# PERIPHERAL_PORT_IO.net
KiCad netlist of a schematic drawn in Altium Designer
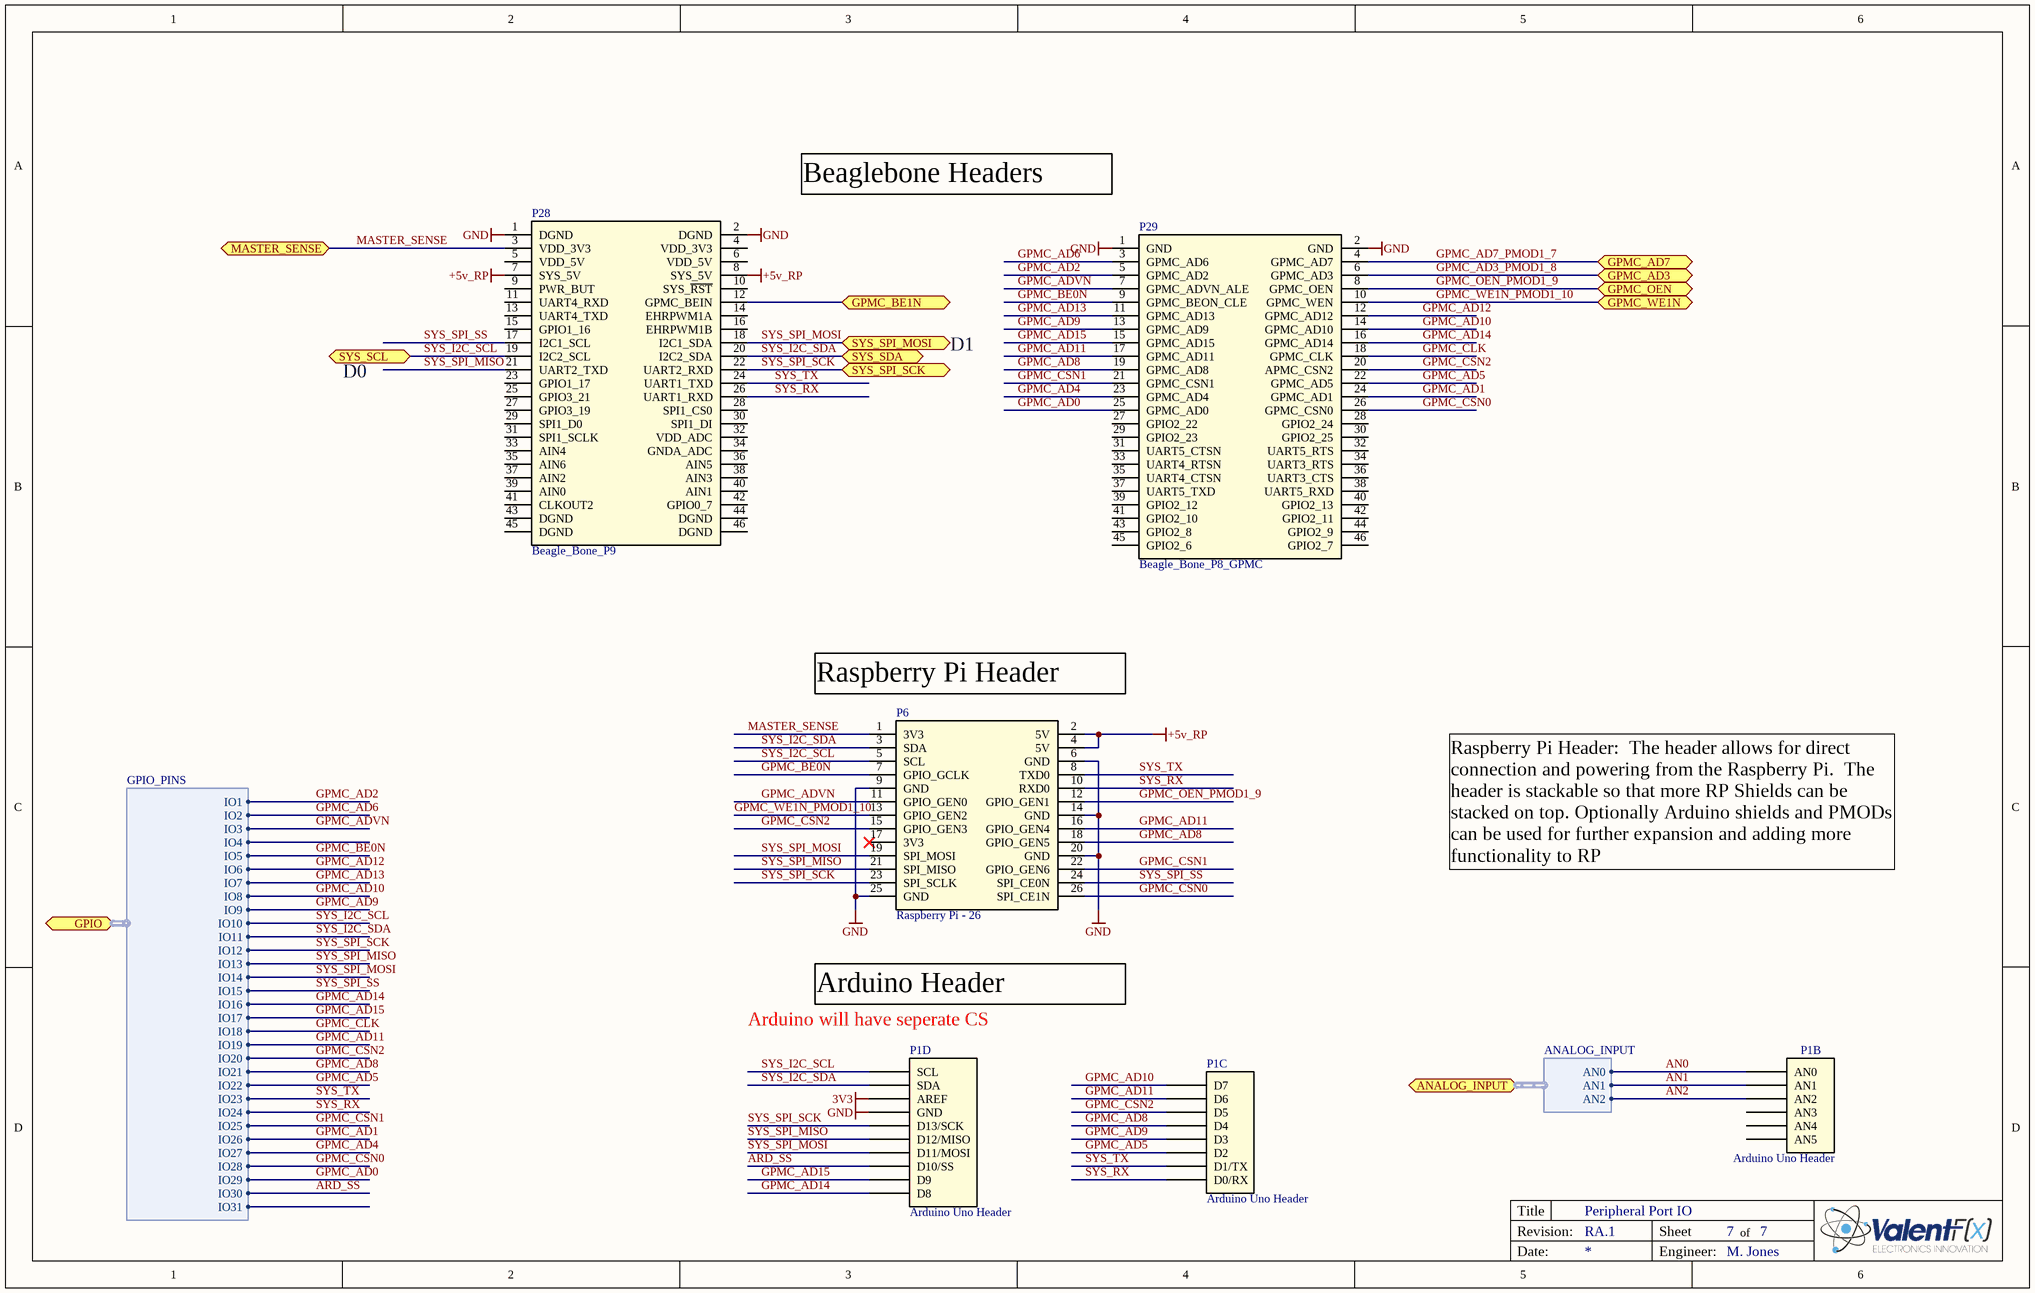
[diagram p0: PERIPHERAL_PORT_IO.SchDoc]

(export (version "E")
  (design (tool "Eeschema 10.0.6"))
  (components
    (comp (ref "P1")
      (value "Arduino Uno Header")
      (footprint "Arduino Shield - smaller Thru")
      (description "Arduino Duem Header")
      (libsource (lib "eConnector") (part "Arduino Shield"))
    )
    (comp (ref "P6")
      (value "Raspberry Pi - 26")
      (footprint "Raspberr Pi - 26")
      (libsource (lib "mConnector") (part "Raspberry Pi - 26"))
    )
    (comp (ref "P28")
      (value "Beagle_Bone_P9")
      (footprint "TSM-116-01-F-DV_TH - SHRUNK")
      (libsource (lib "mConnector") (part "Beagle_Bone_P9"))
    )
    (comp (ref "P29")
      (value "Beagle_Bone_P8_GPMC")
      (footprint "TSM-113-01-F-DV_TH - SHRUNK")
      (libsource (lib "mConnector") (part "Beagle_Bone_P8_GPMC"))
    )
  )
  (nets
    (net (code "3") (name "+5v_RP") (class "Default")
      (node (ref "P28") (pin "7") (pinfunction "SYS_5V_7") (pintype "passive"))
      (node (ref "P28") (pin "8") (pinfunction "SYS_5V_8") (pintype "passive"))
      (node (ref "P6") (pin "2") (pinfunction "5V_2") (pintype "passive"))
      (node (ref "P6") (pin "4") (pinfunction "5V_4") (pintype "passive"))
    )
    (net (code "4") (name "/AN0") (class "Default")
      (node (ref "P1") (pin "B1") (pinfunction "AN0_B1") (pintype "passive"))
    )
    (net (code "5") (name "/AN1") (class "Default")
      (node (ref "P1") (pin "B2") (pinfunction "AN1_B2") (pintype "passive"))
    )
    (net (code "6") (name "/AN2") (class "Default")
      (node (ref "P1") (pin "B3") (pinfunction "AN2_B3") (pintype "passive"))
    )
    (net (code "7") (name "/ARD_SS") (class "Default")
      (node (ref "P1") (pin "D3") (pinfunction "D10/SS_D3") (pintype "passive"))
    )
    (net (code "8") (name "/GPMC_AD0") (class "Default")
      (node (ref "P29") (pin "25") (pinfunction "GPMC_AD0_25") (pintype "passive"))
    )
    (net (code "9") (name "/GPMC_AD1") (class "Default")
      (node (ref "P29") (pin "24") (pinfunction "GPMC_AD1_24") (pintype "passive"))
    )
    (net (code "10") (name "/GPMC_AD2") (class "Default")
      (node (ref "P29") (pin "5") (pinfunction "GPMC_AD2_5") (pintype "passive"))
    )
    (net (code "11") (name "/GPMC_AD3_PMOD1_8") (class "Default")
      (node (ref "P29") (pin "6") (pinfunction "GPMC_AD3_6") (pintype "passive"))
    )
    (net (code "12") (name "/GPMC_AD4") (class "Default")
      (node (ref "P29") (pin "23") (pinfunction "GPMC_AD4_23") (pintype "passive"))
    )
    (net (code "13") (name "/GPMC_AD5") (class "Default")
      (node (ref "P1") (pin "C3") (pinfunction "D2_C3") (pintype "passive"))
      (node (ref "P29") (pin "22") (pinfunction "GPMC_AD5_22") (pintype "passive"))
    )
    (net (code "14") (name "/GPMC_AD6") (class "Default")
      (node (ref "P29") (pin "3") (pinfunction "GPMC_AD6_3") (pintype "passive"))
    )
    (net (code "15") (name "/GPMC_AD7_PMOD1_7") (class "Default")
      (node (ref "P29") (pin "4") (pinfunction "GPMC_AD7_4") (pintype "passive"))
    )
    (net (code "16") (name "/GPMC_AD8") (class "Default")
      (node (ref "P1") (pin "C5") (pinfunction "D4_C5") (pintype "passive"))
      (node (ref "P29") (pin "19") (pinfunction "GPMC_AD8_19") (pintype "passive"))
      (node (ref "P6") (pin "18") (pinfunction "GPIO_GEN5_18") (pintype "passive"))
    )
    (net (code "17") (name "/GPMC_AD9") (class "Default")
      (node (ref "P1") (pin "C4") (pinfunction "D3_C4") (pintype "passive"))
      (node (ref "P29") (pin "13") (pinfunction "GPMC_AD9_13") (pintype "passive"))
    )
    (net (code "18") (name "/GPMC_AD10") (class "Default")
      (node (ref "P1") (pin "C8") (pinfunction "D7_C8") (pintype "passive"))
      (node (ref "P29") (pin "14") (pinfunction "GPMC_AD10_14") (pintype "passive"))
    )
    (net (code "19") (name "/GPMC_AD11") (class "Default")
      (node (ref "P1") (pin "C7") (pinfunction "D6_C7") (pintype "passive"))
      (node (ref "P29") (pin "17") (pinfunction "GPMC_AD11_17") (pintype "passive"))
      (node (ref "P6") (pin "16") (pinfunction "GPIO_GEN4_16") (pintype "passive"))
    )
    (net (code "20") (name "/GPMC_AD12") (class "Default")
      (node (ref "P29") (pin "12") (pinfunction "GPMC_AD12_12") (pintype "passive"))
    )
    (net (code "21") (name "/GPMC_AD13") (class "Default")
      (node (ref "P29") (pin "11") (pinfunction "GPMC_AD13_11") (pintype "passive"))
    )
    (net (code "22") (name "/GPMC_AD14") (class "Default")
      (node (ref "P1") (pin "D1") (pinfunction "D8_D1") (pintype "passive"))
      (node (ref "P29") (pin "16") (pinfunction "GPMC_AD14_16") (pintype "passive"))
    )
    (net (code "23") (name "/GPMC_AD15") (class "Default")
      (node (ref "P1") (pin "D2") (pinfunction "D9_D2") (pintype "passive"))
      (node (ref "P29") (pin "15") (pinfunction "GPMC_AD15_15") (pintype "passive"))
    )
    (net (code "24") (name "/GPMC_ADVN") (class "Default")
      (node (ref "P29") (pin "7") (pinfunction "GPMC_ADVN_ALE_7") (pintype "passive"))
      (node (ref "P6") (pin "11") (pinfunction "GPIO_GEN0_11") (pintype "passive"))
    )
    (net (code "25") (name "/GPMC_BE0N") (class "Default")
      (node (ref "P29") (pin "9") (pinfunction "GPMC_BEON_CLE_9") (pintype "passive"))
      (node (ref "P6") (pin "7") (pinfunction "GPIO_GCLK_7") (pintype "passive"))
    )
    (net (code "26") (name "/GPMC_BE1N") (class "Default")
      (node (ref "P28") (pin "12") (pinfunction "GPMC_BEIN_12") (pintype "passive"))
    )
    (net (code "27") (name "/GPMC_CLK") (class "Default")
      (node (ref "P29") (pin "18") (pinfunction "GPMC_CLK_18") (pintype "passive"))
    )
    (net (code "28") (name "/GPMC_CSN0") (class "Default")
      (node (ref "P29") (pin "26") (pinfunction "GPMC_CSN0_26") (pintype "passive"))
      (node (ref "P6") (pin "26") (pinfunction "SPI_CE1N_26") (pintype "passive"))
    )
    (net (code "29") (name "/GPMC_CSN1") (class "Default")
      (node (ref "P29") (pin "21") (pinfunction "GPMC_CSN1_21") (pintype "passive"))
      (node (ref "P6") (pin "22") (pinfunction "GPIO_GEN6_22") (pintype "passive"))
    )
    (net (code "30") (name "/GPMC_CSN2") (class "Default")
      (node (ref "P1") (pin "C6") (pinfunction "D5_C6") (pintype "passive"))
      (node (ref "P29") (pin "20") (pinfunction "APMC_CSN2_20") (pintype "passive"))
      (node (ref "P6") (pin "15") (pinfunction "GPIO_GEN3_15") (pintype "passive"))
    )
    (net (code "31") (name "/GPMC_OEN_PMOD1_9") (class "Default")
      (node (ref "P29") (pin "8") (pinfunction "GPMC_OEN_8") (pintype "passive"))
      (node (ref "P6") (pin "12") (pinfunction "GPIO_GEN1_12") (pintype "passive"))
    )
    (net (code "32") (name "/GPMC_WE1N_PMOD1_10") (class "Default")
      (node (ref "P29") (pin "10") (pinfunction "GPMC_WEN_10") (pintype "passive"))
      (node (ref "P6") (pin "13") (pinfunction "GPIO_GEN2_13") (pintype "passive"))
    )
    (net (code "33") (name "/MASTER_SENSE") (class "Default")
      (node (ref "P28") (pin "3") (pinfunction "VDD_3V3_3") (pintype "passive"))
      (node (ref "P6") (pin "1") (pinfunction "3V3_1") (pintype "passive"))
    )
    (net (code "34") (name "/SYS_I2C_SCL") (class "Default")
      (node (ref "P1") (pin "D10") (pinfunction "SCL_D10") (pintype "passive"))
      (node (ref "P28") (pin "19") (pinfunction "I2C2_SCL_19") (pintype "passive"))
      (node (ref "P6") (pin "5") (pinfunction "SCL_5") (pintype "passive"))
    )
    (net (code "35") (name "/SYS_I2C_SDA") (class "Default")
      (node (ref "P1") (pin "D9") (pinfunction "SDA_D9") (pintype "passive"))
      (node (ref "P28") (pin "20") (pinfunction "I2C2_SDA_20") (pintype "passive"))
      (node (ref "P6") (pin "3") (pinfunction "SDA_3") (pintype "passive"))
    )
    (net (code "36") (name "/SYS_RX") (class "Default")
      (node (ref "P1") (pin "C1") (pinfunction "D0/RX_C1") (pintype "passive"))
      (node (ref "P28") (pin "26") (pinfunction "UART1_RXD_26") (pintype "passive"))
      (node (ref "P6") (pin "10") (pinfunction "RXD0_10") (pintype "passive"))
    )
    (net (code "37") (name "/SYS_SPI_MISO") (class "Default")
      (node (ref "P1") (pin "D5") (pinfunction "D12/MISO_D5") (pintype "passive"))
      (node (ref "P28") (pin "21") (pinfunction "UART2_TXD_21") (pintype "passive"))
      (node (ref "P6") (pin "21") (pinfunction "SPI_MISO_21") (pintype "passive"))
    )
    (net (code "38") (name "/SYS_SPI_MOSI") (class "Default")
      (node (ref "P1") (pin "D4") (pinfunction "D11/MOSI_D4") (pintype "passive"))
      (node (ref "P28") (pin "18") (pinfunction "I2C1_SDA_18") (pintype "passive"))
      (node (ref "P6") (pin "19") (pinfunction "SPI_MOSI_19") (pintype "passive"))
    )
    (net (code "39") (name "/SYS_SPI_SCK") (class "Default")
      (node (ref "P1") (pin "D6") (pinfunction "D13/SCK_D6") (pintype "passive"))
      (node (ref "P28") (pin "22") (pinfunction "UART2_RXD_22") (pintype "passive"))
      (node (ref "P6") (pin "23") (pinfunction "SPI_SCLK_23") (pintype "passive"))
    )
    (net (code "40") (name "/SYS_SPI_SS") (class "Default")
      (node (ref "P28") (pin "17") (pinfunction "I2C1_SCL_17") (pintype "passive"))
      (node (ref "P6") (pin "24") (pinfunction "SPI_CE0N_24") (pintype "passive"))
    )
    (net (code "41") (name "/SYS_TX") (class "Default")
      (node (ref "P1") (pin "C2") (pinfunction "D1/TX_C2") (pintype "passive"))
      (node (ref "P28") (pin "24") (pinfunction "UART1_TXD_24") (pintype "passive"))
      (node (ref "P6") (pin "8") (pinfunction "TXD0_8") (pintype "passive"))
    )
    (net (code "44") (name "3V3") (class "Default")
      (node (ref "P1") (pin "D8") (pinfunction "AREF_D8") (pintype "passive"))
    )
    (net (code "45") (name "GND") (class "Default")
      (node (ref "P1") (pin "D7") (pinfunction "GND_D7") (pintype "passive"))
      (node (ref "P28") (pin "1") (pinfunction "DGND_1") (pintype "passive"))
      (node (ref "P28") (pin "2") (pinfunction "DGND_2") (pintype "passive"))
      (node (ref "P29") (pin "1") (pinfunction "GND_1") (pintype "passive"))
      (node (ref "P29") (pin "2") (pinfunction "GND_2") (pintype "passive"))
      (node (ref "P6") (pin "14") (pinfunction "GND_14") (pintype "passive"))
      (node (ref "P6") (pin "20") (pinfunction "GND_20") (pintype "passive"))
      (node (ref "P6") (pin "25") (pinfunction "GND_25") (pintype "passive"))
      (node (ref "P6") (pin "6") (pinfunction "GND_6") (pintype "passive"))
      (node (ref "P6") (pin "9") (pinfunction "GND_9") (pintype "passive"))
    )
    (net (code "46") (name "unconnected-(P1B-AN3-PadB4)") (class "Default")
      (node (ref "P1") (pin "B4") (pinfunction "AN3_B4") (pintype "passive"))
    )
    (net (code "47") (name "unconnected-(P1B-AN4-PadB5)") (class "Default")
      (node (ref "P1") (pin "B5") (pinfunction "AN4_B5") (pintype "passive"))
    )
    (net (code "48") (name "unconnected-(P1B-AN5-PadB6)") (class "Default")
      (node (ref "P1") (pin "B6") (pinfunction "AN5_B6") (pintype "passive"))
    )
    (net (code "49") (name "unconnected-(P6-3V3-Pad17)") (class "Default")
      (node (ref "P6") (pin "17") (pinfunction "3V3_17") (pintype "passive+no_connect"))
    )
    (net (code "50") (name "unconnected-(P28-AIN0-Pad39)") (class "Default")
      (node (ref "P28") (pin "39") (pinfunction "AIN0_39") (pintype "passive"))
    )
    (net (code "51") (name "unconnected-(P28-AIN1-Pad40)") (class "Default")
      (node (ref "P28") (pin "40") (pinfunction "AIN1_40") (pintype "passive"))
    )
    (net (code "52") (name "unconnected-(P28-AIN2-Pad37)") (class "Default")
      (node (ref "P28") (pin "37") (pinfunction "AIN2_37") (pintype "passive"))
    )
    (net (code "53") (name "unconnected-(P28-AIN3-Pad38)") (class "Default")
      (node (ref "P28") (pin "38") (pinfunction "AIN3_38") (pintype "passive"))
    )
    (net (code "54") (name "unconnected-(P28-AIN4-Pad33)") (class "Default")
      (node (ref "P28") (pin "33") (pinfunction "AIN4_33") (pintype "passive"))
    )
    (net (code "55") (name "unconnected-(P28-AIN5-Pad36)") (class "Default")
      (node (ref "P28") (pin "36") (pinfunction "AIN5_36") (pintype "passive"))
    )
    (net (code "56") (name "unconnected-(P28-AIN6-Pad35)") (class "Default")
      (node (ref "P28") (pin "35") (pinfunction "AIN6_35") (pintype "passive"))
    )
    (net (code "57") (name "unconnected-(P28-CLKOUT2-Pad41)") (class "Default")
      (node (ref "P28") (pin "41") (pinfunction "CLKOUT2_41") (pintype "passive"))
    )
    (net (code "58") (name "unconnected-(P28-DGND-Pad43)") (class "Default")
      (node (ref "P28") (pin "43") (pinfunction "DGND_43") (pintype "passive"))
    )
    (net (code "59") (name "unconnected-(P28-DGND-Pad44)") (class "Default")
      (node (ref "P28") (pin "44") (pinfunction "DGND_44") (pintype "passive"))
    )
    (net (code "60") (name "unconnected-(P28-DGND-Pad45)") (class "Default")
      (node (ref "P28") (pin "45") (pinfunction "DGND_45") (pintype "passive"))
    )
    (net (code "61") (name "unconnected-(P28-DGND-Pad46)") (class "Default")
      (node (ref "P28") (pin "46") (pinfunction "DGND_46") (pintype "passive"))
    )
    (net (code "62") (name "unconnected-(P28-EHRPWM1A-Pad14)") (class "Default")
      (node (ref "P28") (pin "14") (pinfunction "EHRPWM1A_14") (pintype "passive"))
    )
    (net (code "63") (name "unconnected-(P28-EHRPWM1B-Pad16)") (class "Default")
      (node (ref "P28") (pin "16") (pinfunction "EHRPWM1B_16") (pintype "passive"))
    )
    (net (code "64") (name "unconnected-(P28-GNDA_ADC-Pad34)") (class "Default")
      (node (ref "P28") (pin "34") (pinfunction "GNDA_ADC_34") (pintype "passive"))
    )
    (net (code "65") (name "unconnected-(P28-GPIO0_7-Pad42)") (class "Default")
      (node (ref "P28") (pin "42") (pinfunction "GPIO0_7_42") (pintype "passive"))
    )
    (net (code "66") (name "unconnected-(P28-GPIO1_16-Pad15)") (class "Default")
      (node (ref "P28") (pin "15") (pinfunction "GPIO1_16_15") (pintype "passive"))
    )
    (net (code "67") (name "unconnected-(P28-GPIO1_17-Pad23)") (class "Default")
      (node (ref "P28") (pin "23") (pinfunction "GPIO1_17_23") (pintype "passive"))
    )
    (net (code "68") (name "unconnected-(P28-GPIO3_19-Pad27)") (class "Default")
      (node (ref "P28") (pin "27") (pinfunction "GPIO3_19_27") (pintype "passive"))
    )
    (net (code "69") (name "unconnected-(P28-GPIO3_21-Pad25)") (class "Default")
      (node (ref "P28") (pin "25") (pinfunction "GPIO3_21_25") (pintype "passive"))
    )
    (net (code "70") (name "unconnected-(P28-PWR_BUT-Pad9)") (class "Default")
      (node (ref "P28") (pin "9") (pinfunction "PWR_BUT_9") (pintype "passive"))
    )
    (net (code "71") (name "unconnected-(P28-SPI1_CS0-Pad28)") (class "Default")
      (node (ref "P28") (pin "28") (pinfunction "SPI1_CS0_28") (pintype "passive"))
    )
    (net (code "72") (name "unconnected-(P28-SPI1_D0-Pad29)") (class "Default")
      (node (ref "P28") (pin "29") (pinfunction "SPI1_D0_29") (pintype "passive"))
    )
    (net (code "73") (name "unconnected-(P28-SPI1_DI-Pad30)") (class "Default")
      (node (ref "P28") (pin "30") (pinfunction "SPI1_DI_30") (pintype "passive"))
    )
    (net (code "74") (name "unconnected-(P28-SPI1_SCLK-Pad31)") (class "Default")
      (node (ref "P28") (pin "31") (pinfunction "SPI1_SCLK_31") (pintype "passive"))
    )
    (net (code "75") (name "unconnected-(P28-SYS_~{RST}-Pad10)") (class "Default")
      (node (ref "P28") (pin "10") (pinfunction "SYS_~{RST}_10") (pintype "passive"))
    )
    (net (code "76") (name "unconnected-(P28-UART4_RXD-Pad11)") (class "Default")
      (node (ref "P28") (pin "11") (pinfunction "UART4_RXD_11") (pintype "passive"))
    )
    (net (code "77") (name "unconnected-(P28-UART4_TXD-Pad13)") (class "Default")
      (node (ref "P28") (pin "13") (pinfunction "UART4_TXD_13") (pintype "passive"))
    )
    (net (code "78") (name "unconnected-(P28-VDD_3V3-Pad4)") (class "Default")
      (node (ref "P28") (pin "4") (pinfunction "VDD_3V3_4") (pintype "passive"))
    )
    (net (code "79") (name "unconnected-(P28-VDD_5V-Pad5)") (class "Default")
      (node (ref "P28") (pin "5") (pinfunction "VDD_5V_5") (pintype "passive"))
    )
    (net (code "80") (name "unconnected-(P28-VDD_5V-Pad6)") (class "Default")
      (node (ref "P28") (pin "6") (pinfunction "VDD_5V_6") (pintype "passive"))
    )
    (net (code "81") (name "unconnected-(P28-VDD_ADC-Pad32)") (class "Default")
      (node (ref "P28") (pin "32") (pinfunction "VDD_ADC_32") (pintype "passive"))
    )
    (net (code "82") (name "unconnected-(P29-GPIO2_6-Pad45)") (class "Default")
      (node (ref "P29") (pin "45") (pinfunction "GPIO2_6_45") (pintype "passive"))
    )
    (net (code "83") (name "unconnected-(P29-GPIO2_7-Pad46)") (class "Default")
      (node (ref "P29") (pin "46") (pinfunction "GPIO2_7_46") (pintype "passive"))
    )
    (net (code "84") (name "unconnected-(P29-GPIO2_8-Pad43)") (class "Default")
      (node (ref "P29") (pin "43") (pinfunction "GPIO2_8_43") (pintype "passive"))
    )
    (net (code "85") (name "unconnected-(P29-GPIO2_9-Pad44)") (class "Default")
      (node (ref "P29") (pin "44") (pinfunction "GPIO2_9_44") (pintype "passive"))
    )
    (net (code "86") (name "unconnected-(P29-GPIO2_10-Pad41)") (class "Default")
      (node (ref "P29") (pin "41") (pinfunction "GPIO2_10_41") (pintype "passive"))
    )
    (net (code "87") (name "unconnected-(P29-GPIO2_11-Pad42)") (class "Default")
      (node (ref "P29") (pin "42") (pinfunction "GPIO2_11_42") (pintype "passive"))
    )
    (net (code "88") (name "unconnected-(P29-GPIO2_12-Pad39)") (class "Default")
      (node (ref "P29") (pin "39") (pinfunction "GPIO2_12_39") (pintype "passive"))
    )
    (net (code "89") (name "unconnected-(P29-GPIO2_13-Pad40)") (class "Default")
      (node (ref "P29") (pin "40") (pinfunction "GPIO2_13_40") (pintype "passive"))
    )
    (net (code "90") (name "unconnected-(P29-GPIO2_22-Pad27)") (class "Default")
      (node (ref "P29") (pin "27") (pinfunction "GPIO2_22_27") (pintype "passive"))
    )
    (net (code "91") (name "unconnected-(P29-GPIO2_23-Pad29)") (class "Default")
      (node (ref "P29") (pin "29") (pinfunction "GPIO2_23_29") (pintype "passive"))
    )
    (net (code "92") (name "unconnected-(P29-GPIO2_24-Pad28)") (class "Default")
      (node (ref "P29") (pin "28") (pinfunction "GPIO2_24_28") (pintype "passive"))
    )
    (net (code "93") (name "unconnected-(P29-GPIO2_25-Pad30)") (class "Default")
      (node (ref "P29") (pin "30") (pinfunction "GPIO2_25_30") (pintype "passive"))
    )
    (net (code "94") (name "unconnected-(P29-UART3_CTS-Pad36)") (class "Default")
      (node (ref "P29") (pin "36") (pinfunction "UART3_CTS_36") (pintype "passive"))
    )
    (net (code "95") (name "unconnected-(P29-UART3_RTS-Pad34)") (class "Default")
      (node (ref "P29") (pin "34") (pinfunction "UART3_RTS_34") (pintype "passive"))
    )
    (net (code "96") (name "unconnected-(P29-UART4_CTSN-Pad35)") (class "Default")
      (node (ref "P29") (pin "35") (pinfunction "UART4_CTSN_35") (pintype "passive"))
    )
    (net (code "97") (name "unconnected-(P29-UART4_RTSN-Pad33)") (class "Default")
      (node (ref "P29") (pin "33") (pinfunction "UART4_RTSN_33") (pintype "passive"))
    )
    (net (code "98") (name "unconnected-(P29-UART5_CTSN-Pad31)") (class "Default")
      (node (ref "P29") (pin "31") (pinfunction "UART5_CTSN_31") (pintype "passive"))
    )
    (net (code "99") (name "unconnected-(P29-UART5_RTS-Pad32)") (class "Default")
      (node (ref "P29") (pin "32") (pinfunction "UART5_RTS_32") (pintype "passive"))
    )
    (net (code "100") (name "unconnected-(P29-UART5_RXD-Pad38)") (class "Default")
      (node (ref "P29") (pin "38") (pinfunction "UART5_RXD_38") (pintype "passive"))
    )
    (net (code "101") (name "unconnected-(P29-UART5_TXD-Pad37)") (class "Default")
      (node (ref "P29") (pin "37") (pinfunction "UART5_TXD_37") (pintype "passive"))
    )
  )
)
